# LEDs.net
KiCad netlist of a schematic drawn in Altium Designer
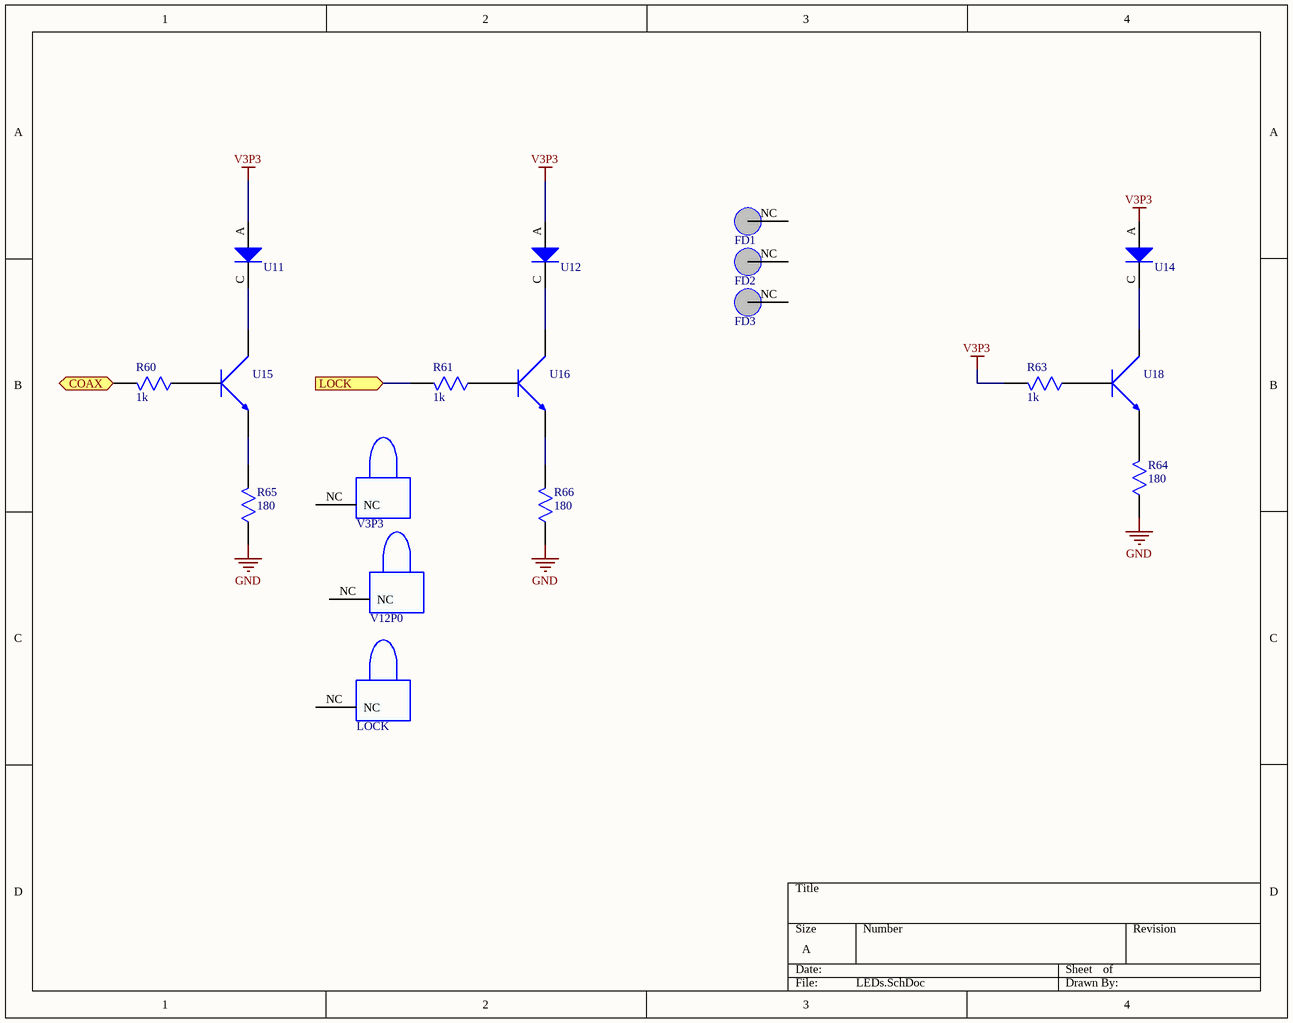
[diagram p0: LEDs.SchDoc]

(export (version "E")
  (design (tool "Eeschema 10.0.6"))
  (components
    (comp (ref "FD1")
      (value "Fiducial Mark")
      (footprint "Fiducial Round")
      (libsource (lib "DA_Component_Library") (part "Fiducial Mark"))
    )
    (comp (ref "FD2")
      (value "Fiducial Mark")
      (footprint "Fiducial Round")
      (libsource (lib "DA_Component_Library") (part "Fiducial Mark"))
    )
    (comp (ref "FD3")
      (value "Fiducial Mark")
      (footprint "Fiducial Round")
      (libsource (lib "DA_Component_Library") (part "Fiducial Mark"))
    )
    (comp (ref "LOCK")
      (value "Light Pipe")
      (footprint "Light Pipe")
      (libsource (lib "DA_Component_Library") (part "Light Pipe"))
    )
    (comp (ref "R60")
      (value "1k")
      (footprint "SMD Resistor 0603")
      (fields (field (name "Comment") "Resistor"))
      (libsource (lib "DA_Component_Library") (part "Resistor"))
    )
    (comp (ref "R61")
      (value "1k")
      (footprint "SMD Resistor 0603")
      (fields (field (name "Comment") "Resistor"))
      (libsource (lib "DA_Component_Library") (part "Resistor"))
    )
    (comp (ref "R63")
      (value "1k")
      (footprint "SMD Resistor 0603")
      (fields (field (name "Comment") "Resistor"))
      (libsource (lib "DA_Component_Library") (part "Resistor"))
    )
    (comp (ref "R64")
      (value "180")
      (footprint "SMD Resistor 0603")
      (fields (field (name "Comment") "Resistor"))
      (libsource (lib "DA_Component_Library") (part "Resistor"))
    )
    (comp (ref "R65")
      (value "180")
      (footprint "SMD Resistor 0603")
      (fields (field (name "Comment") "Resistor"))
      (libsource (lib "DA_Component_Library") (part "Resistor"))
    )
    (comp (ref "R66")
      (value "180")
      (footprint "SMD Resistor 0603")
      (fields (field (name "Comment") "Resistor"))
      (libsource (lib "DA_Component_Library") (part "Resistor"))
    )
    (comp (ref "U11")
      (value "LED")
      (footprint "LED_0603")
      (libsource (lib "DA_Component_Library") (part "LED"))
    )
    (comp (ref "U12")
      (value "LED")
      (footprint "LED_0603")
      (libsource (lib "DA_Component_Library") (part "LED"))
    )
    (comp (ref "U14")
      (value "LED")
      (footprint "LED_0603")
      (libsource (lib "DA_Component_Library") (part "LED"))
    )
    (comp (ref "U15")
      (value "transistor NPN")
      (footprint "SOT23127P600-8N")
      (libsource (lib "DA_Component_Library") (part "transistor NPN"))
    )
    (comp (ref "U16")
      (value "transistor NPN")
      (footprint "SOT23127P600-8N")
      (libsource (lib "DA_Component_Library") (part "transistor NPN"))
    )
    (comp (ref "U18")
      (value "transistor NPN")
      (footprint "SOT23127P600-8N")
      (libsource (lib "DA_Component_Library") (part "transistor NPN"))
    )
    (comp (ref "V3P3")
      (value "Light Pipe")
      (footprint "Light Pipe")
      (libsource (lib "DA_Component_Library") (part "Light Pipe"))
    )
    (comp (ref "V12P0")
      (value "Light Pipe")
      (footprint "Light Pipe")
      (libsource (lib "DA_Component_Library") (part "Light Pipe"))
    )
  )
  (nets
    (net (code "1") (name "/COAX") (class "Default")
      (node (ref "R60") (pin "1") (pinfunction "1_1") (pintype "passive"))
    )
    (net (code "2") (name "/LOCK") (class "Default")
      (node (ref "R61") (pin "1") (pinfunction "1_1") (pintype "passive"))
    )
    (net (code "3") (name "GND") (class "Default")
      (node (ref "R64") (pin "0") (pinfunction "0_0") (pintype "passive"))
      (node (ref "R65") (pin "0") (pinfunction "0_0") (pintype "passive"))
      (node (ref "R66") (pin "0") (pinfunction "0_0") (pintype "passive"))
    )
    (net (code "4") (name "Net-(R60-Pad0)") (class "Default")
      (node (ref "R60") (pin "0") (pinfunction "0_0") (pintype "passive"))
      (node (ref "U15") (pin "B") (pinfunction "B_B") (pintype "passive"))
    )
    (net (code "5") (name "Net-(R61-Pad0)") (class "Default")
      (node (ref "R61") (pin "0") (pinfunction "0_0") (pintype "passive"))
      (node (ref "U16") (pin "B") (pinfunction "B_B") (pintype "passive"))
    )
    (net (code "6") (name "Net-(R63-Pad0)") (class "Default")
      (node (ref "R63") (pin "0") (pinfunction "0_0") (pintype "passive"))
      (node (ref "U18") (pin "B") (pinfunction "B_B") (pintype "passive"))
    )
    (net (code "7") (name "Net-(R64-Pad1)") (class "Default")
      (node (ref "R64") (pin "1") (pinfunction "1_1") (pintype "passive"))
      (node (ref "U18") (pin "E") (pinfunction "E_E") (pintype "passive"))
    )
    (net (code "8") (name "Net-(R65-Pad1)") (class "Default")
      (node (ref "R65") (pin "1") (pinfunction "1_1") (pintype "passive"))
      (node (ref "U15") (pin "E") (pinfunction "E_E") (pintype "passive"))
    )
    (net (code "9") (name "Net-(R66-Pad1)") (class "Default")
      (node (ref "R66") (pin "1") (pinfunction "1_1") (pintype "passive"))
      (node (ref "U16") (pin "E") (pinfunction "E_E") (pintype "passive"))
    )
    (net (code "10") (name "Net-(U11-PadC)") (class "Default")
      (node (ref "U11") (pin "C") (pinfunction "C_C") (pintype "passive"))
      (node (ref "U15") (pin "C") (pinfunction "C_C") (pintype "passive"))
    )
    (net (code "11") (name "Net-(U12-PadC)") (class "Default")
      (node (ref "U12") (pin "C") (pinfunction "C_C") (pintype "passive"))
      (node (ref "U16") (pin "C") (pinfunction "C_C") (pintype "passive"))
    )
    (net (code "12") (name "Net-(U14-PadC)") (class "Default")
      (node (ref "U14") (pin "C") (pinfunction "C_C") (pintype "passive"))
      (node (ref "U18") (pin "C") (pinfunction "C_C") (pintype "passive"))
    )
    (net (code "13") (name "V3P3") (class "Default")
      (node (ref "R63") (pin "1") (pinfunction "1_1") (pintype "passive"))
      (node (ref "U11") (pin "A") (pinfunction "A_A") (pintype "passive"))
      (node (ref "U12") (pin "A") (pinfunction "A_A") (pintype "passive"))
      (node (ref "U14") (pin "A") (pinfunction "A_A") (pintype "passive"))
    )
    (net (code "14") (name "unconnected-(FD1-PadNC)") (class "Default")
      (node (ref "FD1") (pin "NC") (pinfunction "NC_NC") (pintype "passive"))
    )
    (net (code "15") (name "unconnected-(FD2-PadNC)") (class "Default")
      (node (ref "FD2") (pin "NC") (pinfunction "NC_NC") (pintype "passive"))
    )
    (net (code "16") (name "unconnected-(FD3-PadNC)") (class "Default")
      (node (ref "FD3") (pin "NC") (pinfunction "NC_NC") (pintype "passive"))
    )
    (net (code "17") (name "unconnected-(LOCK-PadNC)") (class "Default")
      (node (ref "LOCK") (pin "NC") (pinfunction "NC_NC") (pintype "passive"))
    )
    (net (code "18") (name "unconnected-(V3P3-PadNC)") (class "Default")
      (node (ref "V3P3") (pin "NC") (pinfunction "NC_NC") (pintype "passive"))
    )
    (net (code "19") (name "unconnected-(V12P0-PadNC)") (class "Default")
      (node (ref "V12P0") (pin "NC") (pinfunction "NC_NC") (pintype "passive"))
    )
  )
)
